# RGBKeyboard.net
KiCad netlist of a schematic drawn in EAGLE
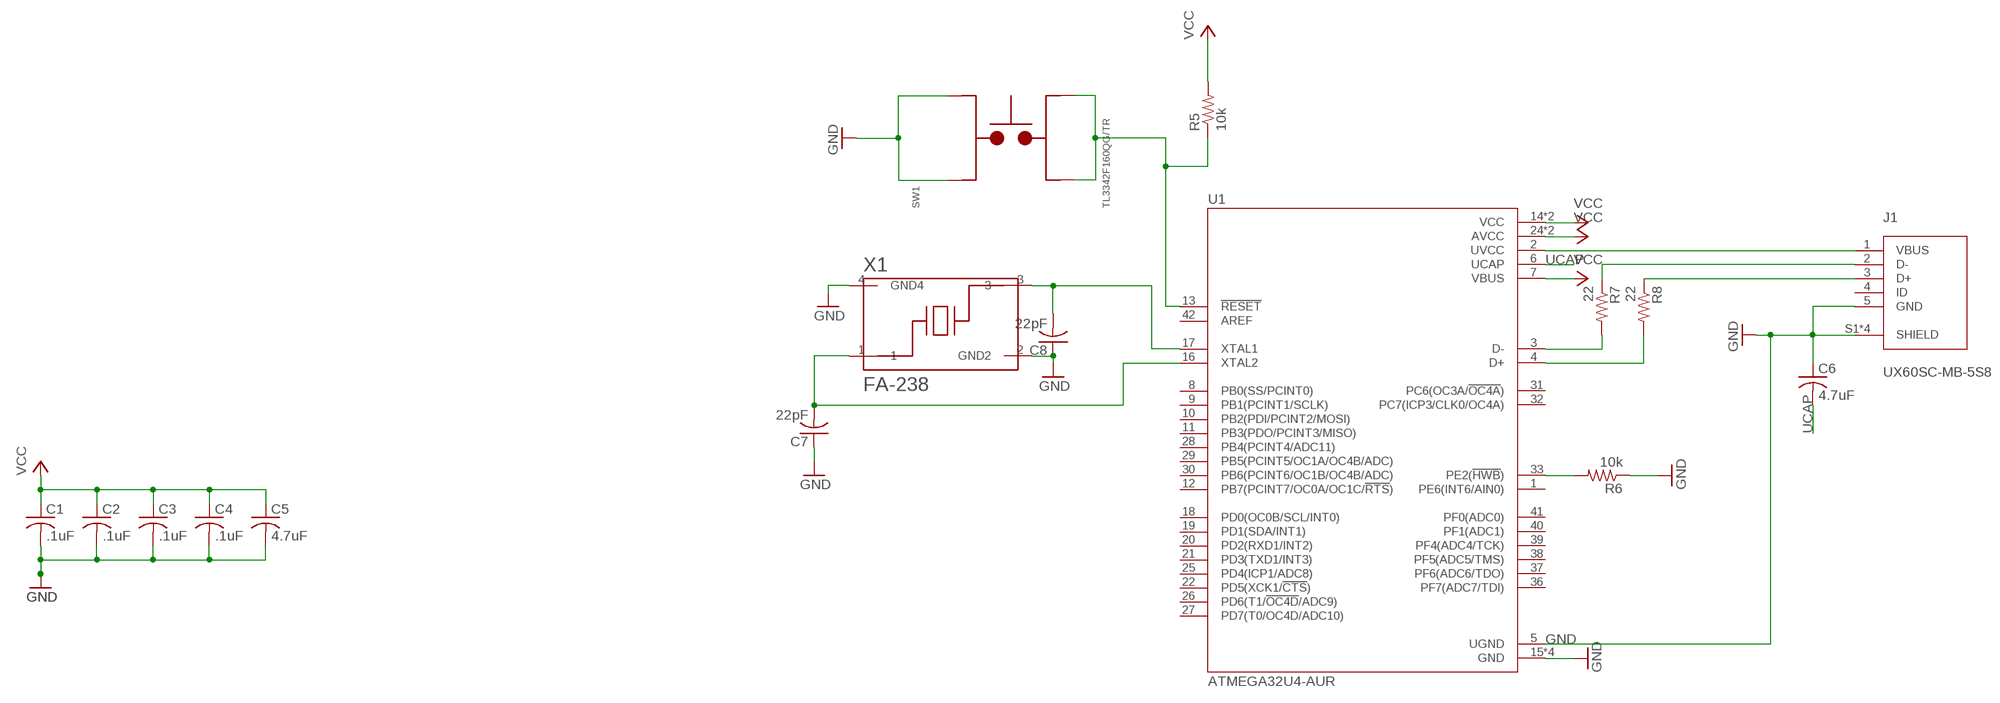
[diagram p0: schematic, sheet 1]
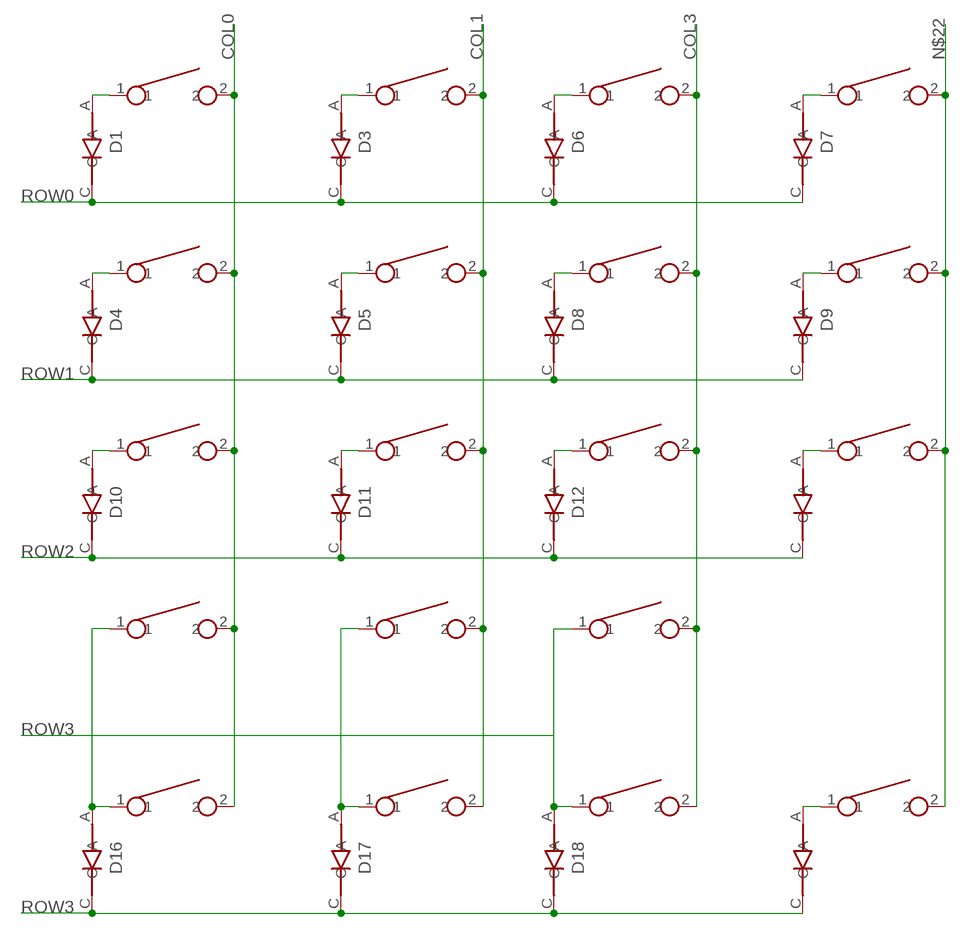
[diagram p1: schematic, sheet 2]

(export (version "E")
  (design (tool "Eeschema 10.0.6"))
  (components
    (comp (ref "C1")
      (value ".1uF")
      (footprint "eagle-import:C0805")
      (libsource (lib "eagle-import") (part "C-USC0805"))
    )
    (comp (ref "C2")
      (value ".1uF")
      (footprint "eagle-import:C0805")
      (libsource (lib "eagle-import") (part "C-USC0805"))
    )
    (comp (ref "C3")
      (value ".1uF")
      (footprint "eagle-import:C0805")
      (libsource (lib "eagle-import") (part "C-USC0805"))
    )
    (comp (ref "C4")
      (value ".1uF")
      (footprint "eagle-import:C0805")
      (libsource (lib "eagle-import") (part "C-USC0805"))
    )
    (comp (ref "C5")
      (value "4.7uF")
      (footprint "eagle-import:C0805")
      (libsource (lib "eagle-import") (part "C-USC0805"))
    )
    (comp (ref "C6")
      (value "4.7uF")
      (footprint "eagle-import:C0805")
      (libsource (lib "eagle-import") (part "C-USC0805"))
    )
    (comp (ref "C7")
      (value "22pF")
      (footprint "eagle-import:C0805")
      (libsource (lib "eagle-import") (part "C-USC0805"))
    )
    (comp (ref "C8")
      (value "22pF")
      (footprint "eagle-import:C0805")
      (libsource (lib "eagle-import") (part "C-USC0805"))
    )
    (comp (ref "J1")
      (value "UX60SC-MB-5S8")
      (footprint "eagle-import:HIROSE_UX60SC-MB-5S8")
      (fields (field (name "MF") "Hirose"))
      (libsource (lib "eagle-import") (part "UX60SC-MB-5S8"))
    )
    (comp (ref "R5")
      (value "10k")
      (footprint "eagle-import:R0805")
      (libsource (lib "eagle-import") (part "R-US_R0805"))
    )
    (comp (ref "R6")
      (value "10k")
      (footprint "eagle-import:R0805")
      (libsource (lib "eagle-import") (part "R-US_R0805"))
    )
    (comp (ref "R7")
      (value "22")
      (footprint "eagle-import:R0805")
      (libsource (lib "eagle-import") (part "R-US_R0805"))
    )
    (comp (ref "R8")
      (value "22")
      (footprint "eagle-import:R0805")
      (libsource (lib "eagle-import") (part "R-US_R0805"))
    )
    (comp (ref "SW1")
      (value "TL3342F160QG/TR")
      (footprint "eagle-import:SW_TL3342F160QG_TR")
      (fields (field (name "MF") "E-Switch"))
      (libsource (lib "eagle-import") (part "TL3342F160QG/TR"))
    )
    (comp (ref "U1")
      (value "ATMEGA32U4-AUR")
      (footprint "eagle-import:QFP80P1200X1200X120-44N")
      (fields (field (name "MF") "Microchip"))
      (libsource (lib "eagle-import") (part "ATMEGA32U4-AUR"))
    )
    (comp (ref "X1")
      (value "FA-238")
      (footprint "eagle-import:OSCCC320X250X70-4N")
      (fields (field (name "MF") "EPSON"))
      (libsource (lib "eagle-import") (part "FA-238"))
    )
    (comp (ref "D1")
      (value "BAV21W-7-F")
      (footprint "eagle-import:SOD3715X135N")
      (fields (field (name "DIGI-KEY_PART_NUMBER") "BAV21W-FDICT-ND") (field (name "MF") "Diodes Inc."))
      (libsource (lib "eagle-import") (part "BAV21W-7-F"))
    )
    (comp (ref "D3")
      (value "BAV21W-7-F")
      (footprint "eagle-import:SOD3715X135N")
      (fields (field (name "DIGI-KEY_PART_NUMBER") "BAV21W-FDICT-ND") (field (name "MF") "Diodes Inc."))
      (libsource (lib "eagle-import") (part "BAV21W-7-F"))
    )
    (comp (ref "D4")
      (value "BAV21W-7-F")
      (footprint "eagle-import:SOD3715X135N")
      (fields (field (name "DIGI-KEY_PART_NUMBER") "BAV21W-FDICT-ND") (field (name "MF") "Diodes Inc."))
      (libsource (lib "eagle-import") (part "BAV21W-7-F"))
    )
    (comp (ref "D5")
      (value "BAV21W-7-F")
      (footprint "eagle-import:SOD3715X135N")
      (fields (field (name "DIGI-KEY_PART_NUMBER") "BAV21W-FDICT-ND") (field (name "MF") "Diodes Inc."))
      (libsource (lib "eagle-import") (part "BAV21W-7-F"))
    )
    (comp (ref "D6")
      (value "BAV21W-7-F")
      (footprint "eagle-import:SOD3715X135N")
      (fields (field (name "DIGI-KEY_PART_NUMBER") "BAV21W-FDICT-ND") (field (name "MF") "Diodes Inc."))
      (libsource (lib "eagle-import") (part "BAV21W-7-F"))
    )
    (comp (ref "D7")
      (value "BAV21W-7-F")
      (footprint "eagle-import:SOD3715X135N")
      (fields (field (name "DIGI-KEY_PART_NUMBER") "BAV21W-FDICT-ND") (field (name "MF") "Diodes Inc."))
      (libsource (lib "eagle-import") (part "BAV21W-7-F"))
    )
    (comp (ref "D8")
      (value "BAV21W-7-F")
      (footprint "eagle-import:SOD3715X135N")
      (fields (field (name "DIGI-KEY_PART_NUMBER") "BAV21W-FDICT-ND") (field (name "MF") "Diodes Inc."))
      (libsource (lib "eagle-import") (part "BAV21W-7-F"))
    )
    (comp (ref "D9")
      (value "BAV21W-7-F")
      (footprint "eagle-import:SOD3715X135N")
      (fields (field (name "DIGI-KEY_PART_NUMBER") "BAV21W-FDICT-ND") (field (name "MF") "Diodes Inc."))
      (libsource (lib "eagle-import") (part "BAV21W-7-F"))
    )
    (comp (ref "D10")
      (value "BAV21W-7-F")
      (footprint "eagle-import:SOD3715X135N")
      (fields (field (name "DIGI-KEY_PART_NUMBER") "BAV21W-FDICT-ND") (field (name "MF") "Diodes Inc."))
      (libsource (lib "eagle-import") (part "BAV21W-7-F"))
    )
    (comp (ref "D11")
      (value "BAV21W-7-F")
      (footprint "eagle-import:SOD3715X135N")
      (fields (field (name "DIGI-KEY_PART_NUMBER") "BAV21W-FDICT-ND") (field (name "MF") "Diodes Inc."))
      (libsource (lib "eagle-import") (part "BAV21W-7-F"))
    )
    (comp (ref "D12")
      (value "BAV21W-7-F")
      (footprint "eagle-import:SOD3715X135N")
      (fields (field (name "DIGI-KEY_PART_NUMBER") "BAV21W-FDICT-ND") (field (name "MF") "Diodes Inc."))
      (libsource (lib "eagle-import") (part "BAV21W-7-F"))
    )
    (comp (ref "D13")
      (value "BAV21W-7-F")
      (footprint "eagle-import:SOD3715X135N")
      (fields (field (name "DIGI-KEY_PART_NUMBER") "BAV21W-FDICT-ND") (field (name "MF") "Diodes Inc."))
      (libsource (lib "eagle-import") (part "BAV21W-7-F"))
    )
    (comp (ref "D16")
      (value "BAV21W-7-F")
      (footprint "eagle-import:SOD3715X135N")
      (fields (field (name "DIGI-KEY_PART_NUMBER") "BAV21W-FDICT-ND") (field (name "MF") "Diodes Inc."))
      (libsource (lib "eagle-import") (part "BAV21W-7-F"))
    )
    (comp (ref "D17")
      (value "BAV21W-7-F")
      (footprint "eagle-import:SOD3715X135N")
      (fields (field (name "DIGI-KEY_PART_NUMBER") "BAV21W-FDICT-ND") (field (name "MF") "Diodes Inc."))
      (libsource (lib "eagle-import") (part "BAV21W-7-F"))
    )
    (comp (ref "D18")
      (value "BAV21W-7-F")
      (footprint "eagle-import:SOD3715X135N")
      (fields (field (name "DIGI-KEY_PART_NUMBER") "BAV21W-FDICT-ND") (field (name "MF") "Diodes Inc."))
      (libsource (lib "eagle-import") (part "BAV21W-7-F"))
    )
    (comp (ref "D19")
      (value "BAV21W-7-F")
      (footprint "eagle-import:SOD3715X135N")
      (fields (field (name "DIGI-KEY_PART_NUMBER") "BAV21W-FDICT-ND") (field (name "MF") "Diodes Inc."))
      (libsource (lib "eagle-import") (part "BAV21W-7-F"))
    )
    (comp (ref "U$1")
      (value "CHERRY_MX")
      (footprint "eagle-import:CHERRY_MX")
      (libsource (lib "eagle-import") (part "CHERRY_MX"))
    )
    (comp (ref "U$2")
      (value "CHERRY_MX")
      (footprint "eagle-import:CHERRY_MX")
      (libsource (lib "eagle-import") (part "CHERRY_MX"))
    )
    (comp (ref "U$3")
      (value "CHERRY_MX")
      (footprint "eagle-import:CHERRY_MX")
      (libsource (lib "eagle-import") (part "CHERRY_MX"))
    )
    (comp (ref "U$4")
      (value "CHERRY_MX")
      (footprint "eagle-import:CHERRY_MX")
      (libsource (lib "eagle-import") (part "CHERRY_MX"))
    )
    (comp (ref "U$5")
      (value "CHERRY_MX")
      (footprint "eagle-import:CHERRY_MX")
      (libsource (lib "eagle-import") (part "CHERRY_MX"))
    )
    (comp (ref "U$6")
      (value "CHERRY_MX")
      (footprint "eagle-import:CHERRY_MX")
      (libsource (lib "eagle-import") (part "CHERRY_MX"))
    )
    (comp (ref "U$7")
      (value "CHERRY_MX")
      (footprint "eagle-import:CHERRY_MX")
      (libsource (lib "eagle-import") (part "CHERRY_MX"))
    )
    (comp (ref "U$8")
      (value "CHERRY_MX")
      (footprint "eagle-import:CHERRY_MX")
      (libsource (lib "eagle-import") (part "CHERRY_MX"))
    )
    (comp (ref "U$9")
      (value "CHERRY_MX")
      (footprint "eagle-import:CHERRY_MX")
      (libsource (lib "eagle-import") (part "CHERRY_MX"))
    )
    (comp (ref "U$10")
      (value "CHERRY_MX")
      (footprint "eagle-import:CHERRY_MX")
      (libsource (lib "eagle-import") (part "CHERRY_MX"))
    )
    (comp (ref "U$11")
      (value "CHERRY_MX")
      (footprint "eagle-import:CHERRY_MX")
      (libsource (lib "eagle-import") (part "CHERRY_MX"))
    )
    (comp (ref "U$12")
      (value "CHERRY_MX")
      (footprint "eagle-import:CHERRY_MX")
      (libsource (lib "eagle-import") (part "CHERRY_MX"))
    )
    (comp (ref "U$13")
      (value "CHERRY_MXCHERRY_MX_1_2")
      (footprint "eagle-import:CHERRY_MX_1_2")
      (libsource (lib "eagle-import") (part "CHERRY_MXCHERRY_MX_1_2"))
    )
    (comp (ref "U$14")
      (value "CHERRY_MXCHERRY_MX_1_2")
      (footprint "eagle-import:CHERRY_MX_1_2")
      (libsource (lib "eagle-import") (part "CHERRY_MXCHERRY_MX_1_2"))
    )
    (comp (ref "U$15")
      (value "CHERRY_MXCHERRY_MX_1_2")
      (footprint "eagle-import:CHERRY_MX_1_2")
      (libsource (lib "eagle-import") (part "CHERRY_MXCHERRY_MX_1_2"))
    )
    (comp (ref "U$16")
      (value "CHERRY_MX")
      (footprint "eagle-import:CHERRY_MX")
      (libsource (lib "eagle-import") (part "CHERRY_MX"))
    )
    (comp (ref "U$17")
      (value "CHERRY_MX")
      (footprint "eagle-import:CHERRY_MX")
      (libsource (lib "eagle-import") (part "CHERRY_MX"))
    )
    (comp (ref "U$18")
      (value "CHERRY_MX")
      (footprint "eagle-import:CHERRY_MX")
      (libsource (lib "eagle-import") (part "CHERRY_MX"))
    )
    (comp (ref "U$19")
      (value "CHERRY_MX")
      (footprint "eagle-import:CHERRY_MX")
      (libsource (lib "eagle-import") (part "CHERRY_MX"))
    )
  )
  (nets
    (net (code "1") (name "COL0") (class "Default")
      (node (ref "U$1") (pin "2") (pinfunction "2_2") (pintype "bidirectional"))
      (node (ref "U$13") (pin "2") (pinfunction "2_2") (pintype "bidirectional"))
      (node (ref "U$17") (pin "2") (pinfunction "2_2") (pintype "bidirectional"))
      (node (ref "U$2") (pin "2") (pinfunction "2_2") (pintype "bidirectional"))
      (node (ref "U$3") (pin "2") (pinfunction "2_2") (pintype "bidirectional"))
    )
    (net (code "2") (name "COL1") (class "Default")
      (node (ref "U$14") (pin "2") (pinfunction "2_2") (pintype "bidirectional"))
      (node (ref "U$18") (pin "2") (pinfunction "2_2") (pintype "bidirectional"))
      (node (ref "U$4") (pin "2") (pinfunction "2_2") (pintype "bidirectional"))
      (node (ref "U$5") (pin "2") (pinfunction "2_2") (pintype "bidirectional"))
      (node (ref "U$6") (pin "2") (pinfunction "2_2") (pintype "bidirectional"))
    )
    (net (code "3") (name "COL3") (class "Default")
      (node (ref "U$15") (pin "2") (pinfunction "2_2") (pintype "bidirectional"))
      (node (ref "U$19") (pin "2") (pinfunction "2_2") (pintype "bidirectional"))
      (node (ref "U$7") (pin "2") (pinfunction "2_2") (pintype "bidirectional"))
      (node (ref "U$8") (pin "2") (pinfunction "2_2") (pintype "bidirectional"))
      (node (ref "U$9") (pin "2") (pinfunction "2_2") (pintype "bidirectional"))
    )
    (net (code "4") (name "GND") (class "Default")
      (node (ref "C1") (pin "2") (pinfunction "2_2") (pintype "passive"))
      (node (ref "C2") (pin "2") (pinfunction "2_2") (pintype "passive"))
      (node (ref "C3") (pin "2") (pinfunction "2_2") (pintype "passive"))
      (node (ref "C4") (pin "2") (pinfunction "2_2") (pintype "passive"))
      (node (ref "C5") (pin "2") (pinfunction "2_2") (pintype "passive"))
      (node (ref "C6") (pin "1") (pinfunction "1_1") (pintype "passive"))
      (node (ref "C7") (pin "1") (pinfunction "1_1") (pintype "passive"))
      (node (ref "C8") (pin "1") (pinfunction "1_1") (pintype "passive"))
      (node (ref "J1") (pin "5") (pinfunction "GND_5") (pintype "power_in"))
      (node (ref "J1") (pin "S1") (pinfunction "SHIELD_S1") (pintype "power_in"))
      (node (ref "J1") (pin "S2") (pinfunction "SHIELD_S2") (pintype "power_in"))
      (node (ref "J1") (pin "S3") (pinfunction "SHIELD_S3") (pintype "power_in"))
      (node (ref "J1") (pin "S4") (pinfunction "SHIELD_S4") (pintype "power_in"))
      (node (ref "R6") (pin "1") (pinfunction "1_1") (pintype "passive"))
      (node (ref "SW1") (pin "3") (pinfunction "3_3") (pintype "passive"))
      (node (ref "SW1") (pin "4") (pinfunction "4_4") (pintype "passive"))
      (node (ref "U1") (pin "15") (pinfunction "GND_15") (pintype "power_in"))
      (node (ref "U1") (pin "23") (pinfunction "GND_23") (pintype "power_in"))
      (node (ref "U1") (pin "35") (pinfunction "GND_35") (pintype "power_in"))
      (node (ref "U1") (pin "43") (pinfunction "GND_43") (pintype "power_in"))
      (node (ref "U1") (pin "5") (pinfunction "UGND_5") (pintype "power_in"))
      (node (ref "X1") (pin "2") (pinfunction "GND2_2") (pintype "passive"))
      (node (ref "X1") (pin "4") (pinfunction "GND4_4") (pintype "passive"))
    )
    (net (code "5") (name "N$22") (class "Default")
      (node (ref "U$10") (pin "2") (pinfunction "2_2") (pintype "bidirectional"))
      (node (ref "U$11") (pin "2") (pinfunction "2_2") (pintype "bidirectional"))
      (node (ref "U$12") (pin "2") (pinfunction "2_2") (pintype "bidirectional"))
      (node (ref "U$16") (pin "2") (pinfunction "2_2") (pintype "bidirectional"))
    )
    (net (code "6") (name "Net-(D1-PadA)") (class "Default")
      (node (ref "D1") (pin "A") (pinfunction "A_A") (pintype "passive"))
      (node (ref "U$1") (pin "1") (pinfunction "1_1") (pintype "bidirectional"))
    )
    (net (code "7") (name "Net-(D3-PadA)") (class "Default")
      (node (ref "D3") (pin "A") (pinfunction "A_A") (pintype "passive"))
      (node (ref "U$4") (pin "1") (pinfunction "1_1") (pintype "bidirectional"))
    )
    (net (code "8") (name "Net-(D4-PadA)") (class "Default")
      (node (ref "D4") (pin "A") (pinfunction "A_A") (pintype "passive"))
      (node (ref "U$2") (pin "1") (pinfunction "1_1") (pintype "bidirectional"))
    )
    (net (code "9") (name "Net-(D5-PadA)") (class "Default")
      (node (ref "D5") (pin "A") (pinfunction "A_A") (pintype "passive"))
      (node (ref "U$5") (pin "1") (pinfunction "1_1") (pintype "bidirectional"))
    )
    (net (code "10") (name "Net-(D6-PadA)") (class "Default")
      (node (ref "D6") (pin "A") (pinfunction "A_A") (pintype "passive"))
      (node (ref "U$7") (pin "1") (pinfunction "1_1") (pintype "bidirectional"))
    )
    (net (code "11") (name "Net-(D7-PadA)") (class "Default")
      (node (ref "D7") (pin "A") (pinfunction "A_A") (pintype "passive"))
      (node (ref "U$12") (pin "1") (pinfunction "1_1") (pintype "bidirectional"))
    )
    (net (code "12") (name "Net-(D8-PadA)") (class "Default")
      (node (ref "D8") (pin "A") (pinfunction "A_A") (pintype "passive"))
      (node (ref "U$8") (pin "1") (pinfunction "1_1") (pintype "bidirectional"))
    )
    (net (code "13") (name "Net-(D9-PadA)") (class "Default")
      (node (ref "D9") (pin "A") (pinfunction "A_A") (pintype "passive"))
      (node (ref "U$10") (pin "1") (pinfunction "1_1") (pintype "bidirectional"))
    )
    (net (code "14") (name "Net-(D10-PadA)") (class "Default")
      (node (ref "D10") (pin "A") (pinfunction "A_A") (pintype "passive"))
      (node (ref "U$3") (pin "1") (pinfunction "1_1") (pintype "bidirectional"))
    )
    (net (code "15") (name "Net-(D11-PadA)") (class "Default")
      (node (ref "D11") (pin "A") (pinfunction "A_A") (pintype "passive"))
      (node (ref "U$6") (pin "1") (pinfunction "1_1") (pintype "bidirectional"))
    )
    (net (code "16") (name "Net-(D12-PadA)") (class "Default")
      (node (ref "D12") (pin "A") (pinfunction "A_A") (pintype "passive"))
      (node (ref "U$9") (pin "1") (pinfunction "1_1") (pintype "bidirectional"))
    )
    (net (code "17") (name "Net-(D13-PadA)") (class "Default")
      (node (ref "D13") (pin "A") (pinfunction "A_A") (pintype "passive"))
      (node (ref "U$11") (pin "1") (pinfunction "1_1") (pintype "bidirectional"))
    )
    (net (code "18") (name "Net-(D16-PadA)") (class "Default")
      (node (ref "D16") (pin "A") (pinfunction "A_A") (pintype "passive"))
      (node (ref "U$13") (pin "1") (pinfunction "1_1") (pintype "bidirectional"))
      (node (ref "U$17") (pin "1") (pinfunction "1_1") (pintype "bidirectional"))
    )
    (net (code "19") (name "Net-(D17-PadA)") (class "Default")
      (node (ref "D17") (pin "A") (pinfunction "A_A") (pintype "passive"))
      (node (ref "U$14") (pin "1") (pinfunction "1_1") (pintype "bidirectional"))
      (node (ref "U$18") (pin "1") (pinfunction "1_1") (pintype "bidirectional"))
    )
    (net (code "20") (name "Net-(D18-PadA)") (class "Default")
      (node (ref "D18") (pin "A") (pinfunction "A_A") (pintype "passive"))
      (node (ref "U$15") (pin "1") (pinfunction "1_1") (pintype "bidirectional"))
      (node (ref "U$19") (pin "1") (pinfunction "1_1") (pintype "bidirectional"))
    )
    (net (code "21") (name "Net-(D19-PadA)") (class "Default")
      (node (ref "D19") (pin "A") (pinfunction "A_A") (pintype "passive"))
      (node (ref "U$16") (pin "1") (pinfunction "1_1") (pintype "bidirectional"))
    )
    (net (code "22") (name "Net-(J1-D+)") (class "Default")
      (node (ref "J1") (pin "3") (pinfunction "D+_3") (pintype "bidirectional"))
      (node (ref "R8") (pin "1") (pinfunction "1_1") (pintype "passive"))
    )
    (net (code "23") (name "Net-(J1-D-)") (class "Default")
      (node (ref "J1") (pin "2") (pinfunction "D-_2") (pintype "bidirectional"))
      (node (ref "R7") (pin "1") (pinfunction "1_1") (pintype "passive"))
    )
    (net (code "24") (name "Net-(J1-VBUS)") (class "Default")
      (node (ref "J1") (pin "1") (pinfunction "VBUS_1") (pintype "power_in"))
      (node (ref "U1") (pin "2") (pinfunction "UVCC_2") (pintype "power_in"))
    )
    (net (code "25") (name "Net-(U1-D+)") (class "Default")
      (node (ref "R8") (pin "2") (pinfunction "2_2") (pintype "passive"))
      (node (ref "U1") (pin "4") (pinfunction "D+_4") (pintype "bidirectional"))
    )
    (net (code "26") (name "Net-(U1-D-)") (class "Default")
      (node (ref "R7") (pin "2") (pinfunction "2_2") (pintype "passive"))
      (node (ref "U1") (pin "3") (pinfunction "D-_3") (pintype "bidirectional"))
    )
    (net (code "27") (name "Net-(U1-PE2(~{HWB}))") (class "Default")
      (node (ref "R6") (pin "2") (pinfunction "2_2") (pintype "passive"))
      (node (ref "U1") (pin "33") (pinfunction "PE2(~{HWB})_33") (pintype "bidirectional"))
    )
    (net (code "28") (name "Net-(U1-XTAL1)") (class "Default")
      (node (ref "C8") (pin "2") (pinfunction "2_2") (pintype "passive"))
      (node (ref "U1") (pin "17") (pinfunction "XTAL1_17") (pintype "input"))
      (node (ref "X1") (pin "3") (pinfunction "3_3") (pintype "passive"))
    )
    (net (code "29") (name "Net-(U1-XTAL2)") (class "Default")
      (node (ref "C7") (pin "2") (pinfunction "2_2") (pintype "passive"))
      (node (ref "U1") (pin "16") (pinfunction "XTAL2_16") (pintype "output"))
      (node (ref "X1") (pin "1") (pinfunction "1_1") (pintype "passive"))
    )
    (net (code "30") (name "Net-(U1-~{RESET})") (class "Default")
      (node (ref "R5") (pin "1") (pinfunction "1_1") (pintype "passive"))
      (node (ref "SW1") (pin "1") (pinfunction "1_1") (pintype "passive"))
      (node (ref "SW1") (pin "2") (pinfunction "2_2") (pintype "passive"))
      (node (ref "U1") (pin "13") (pinfunction "~{RESET}_13") (pintype "input"))
    )
    (net (code "31") (name "ROW0") (class "Default")
      (node (ref "D1") (pin "C") (pinfunction "C_C") (pintype "passive"))
      (node (ref "D3") (pin "C") (pinfunction "C_C") (pintype "passive"))
      (node (ref "D6") (pin "C") (pinfunction "C_C") (pintype "passive"))
      (node (ref "D7") (pin "C") (pinfunction "C_C") (pintype "passive"))
    )
    (net (code "32") (name "ROW1") (class "Default")
      (node (ref "D4") (pin "C") (pinfunction "C_C") (pintype "passive"))
      (node (ref "D5") (pin "C") (pinfunction "C_C") (pintype "passive"))
      (node (ref "D8") (pin "C") (pinfunction "C_C") (pintype "passive"))
      (node (ref "D9") (pin "C") (pinfunction "C_C") (pintype "passive"))
    )
    (net (code "33") (name "ROW2") (class "Default")
      (node (ref "D10") (pin "C") (pinfunction "C_C") (pintype "passive"))
      (node (ref "D11") (pin "C") (pinfunction "C_C") (pintype "passive"))
      (node (ref "D12") (pin "C") (pinfunction "C_C") (pintype "passive"))
      (node (ref "D13") (pin "C") (pinfunction "C_C") (pintype "passive"))
    )
    (net (code "34") (name "ROW3") (class "Default")
      (node (ref "D16") (pin "C") (pinfunction "C_C") (pintype "passive"))
      (node (ref "D17") (pin "C") (pinfunction "C_C") (pintype "passive"))
      (node (ref "D18") (pin "C") (pinfunction "C_C") (pintype "passive"))
      (node (ref "D19") (pin "C") (pinfunction "C_C") (pintype "passive"))
    )
    (net (code "35") (name "UCAP") (class "Default")
      (node (ref "C6") (pin "2") (pinfunction "2_2") (pintype "passive"))
      (node (ref "U1") (pin "6") (pinfunction "UCAP_6") (pintype "power_in"))
    )
    (net (code "36") (name "VCC") (class "Default")
      (node (ref "C1") (pin "1") (pinfunction "1_1") (pintype "passive"))
      (node (ref "C2") (pin "1") (pinfunction "1_1") (pintype "passive"))
      (node (ref "C3") (pin "1") (pinfunction "1_1") (pintype "passive"))
      (node (ref "C4") (pin "1") (pinfunction "1_1") (pintype "passive"))
      (node (ref "C5") (pin "1") (pinfunction "1_1") (pintype "passive"))
      (node (ref "R5") (pin "2") (pinfunction "2_2") (pintype "passive"))
      (node (ref "U1") (pin "14") (pinfunction "VCC_14") (pintype "power_in"))
      (node (ref "U1") (pin "24") (pinfunction "AVCC_24") (pintype "power_in"))
      (node (ref "U1") (pin "34") (pinfunction "VCC_34") (pintype "power_in"))
      (node (ref "U1") (pin "44") (pinfunction "AVCC_44") (pintype "power_in"))
      (node (ref "U1") (pin "7") (pinfunction "VBUS_7") (pintype "power_in"))
    )
    (net (code "37") (name "unconnected-(J1-ID-Pad4)") (class "Default")
      (node (ref "J1") (pin "4") (pinfunction "ID_4") (pintype "bidirectional"))
    )
    (net (code "38") (name "unconnected-(U1-AREF-Pad42)") (class "Default")
      (node (ref "U1") (pin "42") (pinfunction "AREF_42") (pintype "input"))
    )
    (net (code "39") (name "unconnected-(U1-PB0(SS{slash}PCINT0)-Pad8)") (class "Default")
      (node (ref "U1") (pin "8") (pinfunction "PB0(SS/PCINT0)_8") (pintype "bidirectional"))
    )
    (net (code "40") (name "unconnected-(U1-PB1(PCINT1{slash}SCLK)-Pad9)") (class "Default")
      (node (ref "U1") (pin "9") (pinfunction "PB1(PCINT1/SCLK)_9") (pintype "bidirectional"))
    )
    (net (code "41") (name "unconnected-(U1-PB2(PDI{slash}PCINT2{slash}MOSI)-Pad10)") (class "Default")
      (node (ref "U1") (pin "10") (pinfunction "PB2(PDI/PCINT2/MOSI)_10") (pintype "bidirectional"))
    )
    (net (code "42") (name "unconnected-(U1-PB3(PDO{slash}PCINT3{slash}MISO)-Pad11)") (class "Default")
      (node (ref "U1") (pin "11") (pinfunction "PB3(PDO/PCINT3/MISO)_11") (pintype "bidirectional"))
    )
    (net (code "43") (name "unconnected-(U1-PB4(PCINT4{slash}ADC11)-Pad28)") (class "Default")
      (node (ref "U1") (pin "28") (pinfunction "PB4(PCINT4/ADC11)_28") (pintype "bidirectional"))
    )
    (net (code "44") (name "unconnected-(U1-PB5(PCINT5{slash}OC1A{slash}OC4B{slash}ADC)-Pad29)") (class "Default")
      (node (ref "U1") (pin "29") (pinfunction "PB5(PCINT5/OC1A/OC4B/ADC)_29") (pintype "bidirectional"))
    )
    (net (code "45") (name "unconnected-(U1-PB6(PCINT6{slash}OC1B{slash}OC4B{slash}ADC)-Pad30)") (class "Default")
      (node (ref "U1") (pin "30") (pinfunction "PB6(PCINT6/OC1B/OC4B/ADC)_30") (pintype "bidirectional"))
    )
    (net (code "46") (name "unconnected-(U1-PB7(PCINT7{slash}OC0A{slash}OC1C{slash}~{RTS})-Pad12)") (class "Default")
      (node (ref "U1") (pin "12") (pinfunction "PB7(PCINT7/OC0A/OC1C/~{RTS})_12") (pintype "bidirectional"))
    )
    (net (code "47") (name "unconnected-(U1-PC6(OC3A{slash}~{OC4A})-Pad31)") (class "Default")
      (node (ref "U1") (pin "31") (pinfunction "PC6(OC3A/~{OC4A})_31") (pintype "bidirectional"))
    )
    (net (code "48") (name "unconnected-(U1-PC7(ICP3{slash}CLK0{slash}OC4A)-Pad32)") (class "Default")
      (node (ref "U1") (pin "32") (pinfunction "PC7(ICP3/CLK0/OC4A)_32") (pintype "bidirectional"))
    )
    (net (code "49") (name "unconnected-(U1-PD0(OC0B{slash}SCL{slash}INT0)-Pad18)") (class "Default")
      (node (ref "U1") (pin "18") (pinfunction "PD0(OC0B/SCL/INT0)_18") (pintype "bidirectional"))
    )
    (net (code "50") (name "unconnected-(U1-PD1(SDA{slash}INT1)-Pad19)") (class "Default")
      (node (ref "U1") (pin "19") (pinfunction "PD1(SDA/INT1)_19") (pintype "bidirectional"))
    )
    (net (code "51") (name "unconnected-(U1-PD2(RXD1{slash}INT2)-Pad20)") (class "Default")
      (node (ref "U1") (pin "20") (pinfunction "PD2(RXD1/INT2)_20") (pintype "bidirectional"))
    )
    (net (code "52") (name "unconnected-(U1-PD3(TXD1{slash}INT3)-Pad21)") (class "Default")
      (node (ref "U1") (pin "21") (pinfunction "PD3(TXD1/INT3)_21") (pintype "bidirectional"))
    )
    (net (code "53") (name "unconnected-(U1-PD4(ICP1{slash}ADC8)-Pad25)") (class "Default")
      (node (ref "U1") (pin "25") (pinfunction "PD4(ICP1/ADC8)_25") (pintype "bidirectional"))
    )
    (net (code "54") (name "unconnected-(U1-PD5(XCK1{slash}~{CTS})-Pad22)") (class "Default")
      (node (ref "U1") (pin "22") (pinfunction "PD5(XCK1/~{CTS})_22") (pintype "bidirectional"))
    )
    (net (code "55") (name "unconnected-(U1-PD6(T1{slash}~{OC4D}{slash}ADC9)-Pad26)") (class "Default")
      (node (ref "U1") (pin "26") (pinfunction "PD6(T1/~{OC4D}/ADC9)_26") (pintype "bidirectional"))
    )
    (net (code "56") (name "unconnected-(U1-PD7(T0{slash}OC4D{slash}ADC10)-Pad27)") (class "Default")
      (node (ref "U1") (pin "27") (pinfunction "PD7(T0/OC4D/ADC10)_27") (pintype "bidirectional"))
    )
    (net (code "57") (name "unconnected-(U1-PE6(INT6{slash}AIN0)-Pad1)") (class "Default")
      (node (ref "U1") (pin "1") (pinfunction "PE6(INT6/AIN0)_1") (pintype "bidirectional"))
    )
    (net (code "58") (name "unconnected-(U1-PF0(ADC0)-Pad41)") (class "Default")
      (node (ref "U1") (pin "41") (pinfunction "PF0(ADC0)_41") (pintype "bidirectional"))
    )
    (net (code "59") (name "unconnected-(U1-PF1(ADC1)-Pad40)") (class "Default")
      (node (ref "U1") (pin "40") (pinfunction "PF1(ADC1)_40") (pintype "bidirectional"))
    )
    (net (code "60") (name "unconnected-(U1-PF4(ADC4{slash}TCK)-Pad39)") (class "Default")
      (node (ref "U1") (pin "39") (pinfunction "PF4(ADC4/TCK)_39") (pintype "bidirectional"))
    )
    (net (code "61") (name "unconnected-(U1-PF5(ADC5{slash}TMS)-Pad38)") (class "Default")
      (node (ref "U1") (pin "38") (pinfunction "PF5(ADC5/TMS)_38") (pintype "bidirectional"))
    )
    (net (code "62") (name "unconnected-(U1-PF6(ADC6{slash}TDO)-Pad37)") (class "Default")
      (node (ref "U1") (pin "37") (pinfunction "PF6(ADC6/TDO)_37") (pintype "bidirectional"))
    )
    (net (code "63") (name "unconnected-(U1-PF7(ADC7{slash}TDI)-Pad36)") (class "Default")
      (node (ref "U1") (pin "36") (pinfunction "PF7(ADC7/TDI)_36") (pintype "bidirectional"))
    )
  )
)
